# Conversion.net
KiCad netlist of a schematic drawn in Altium Designer
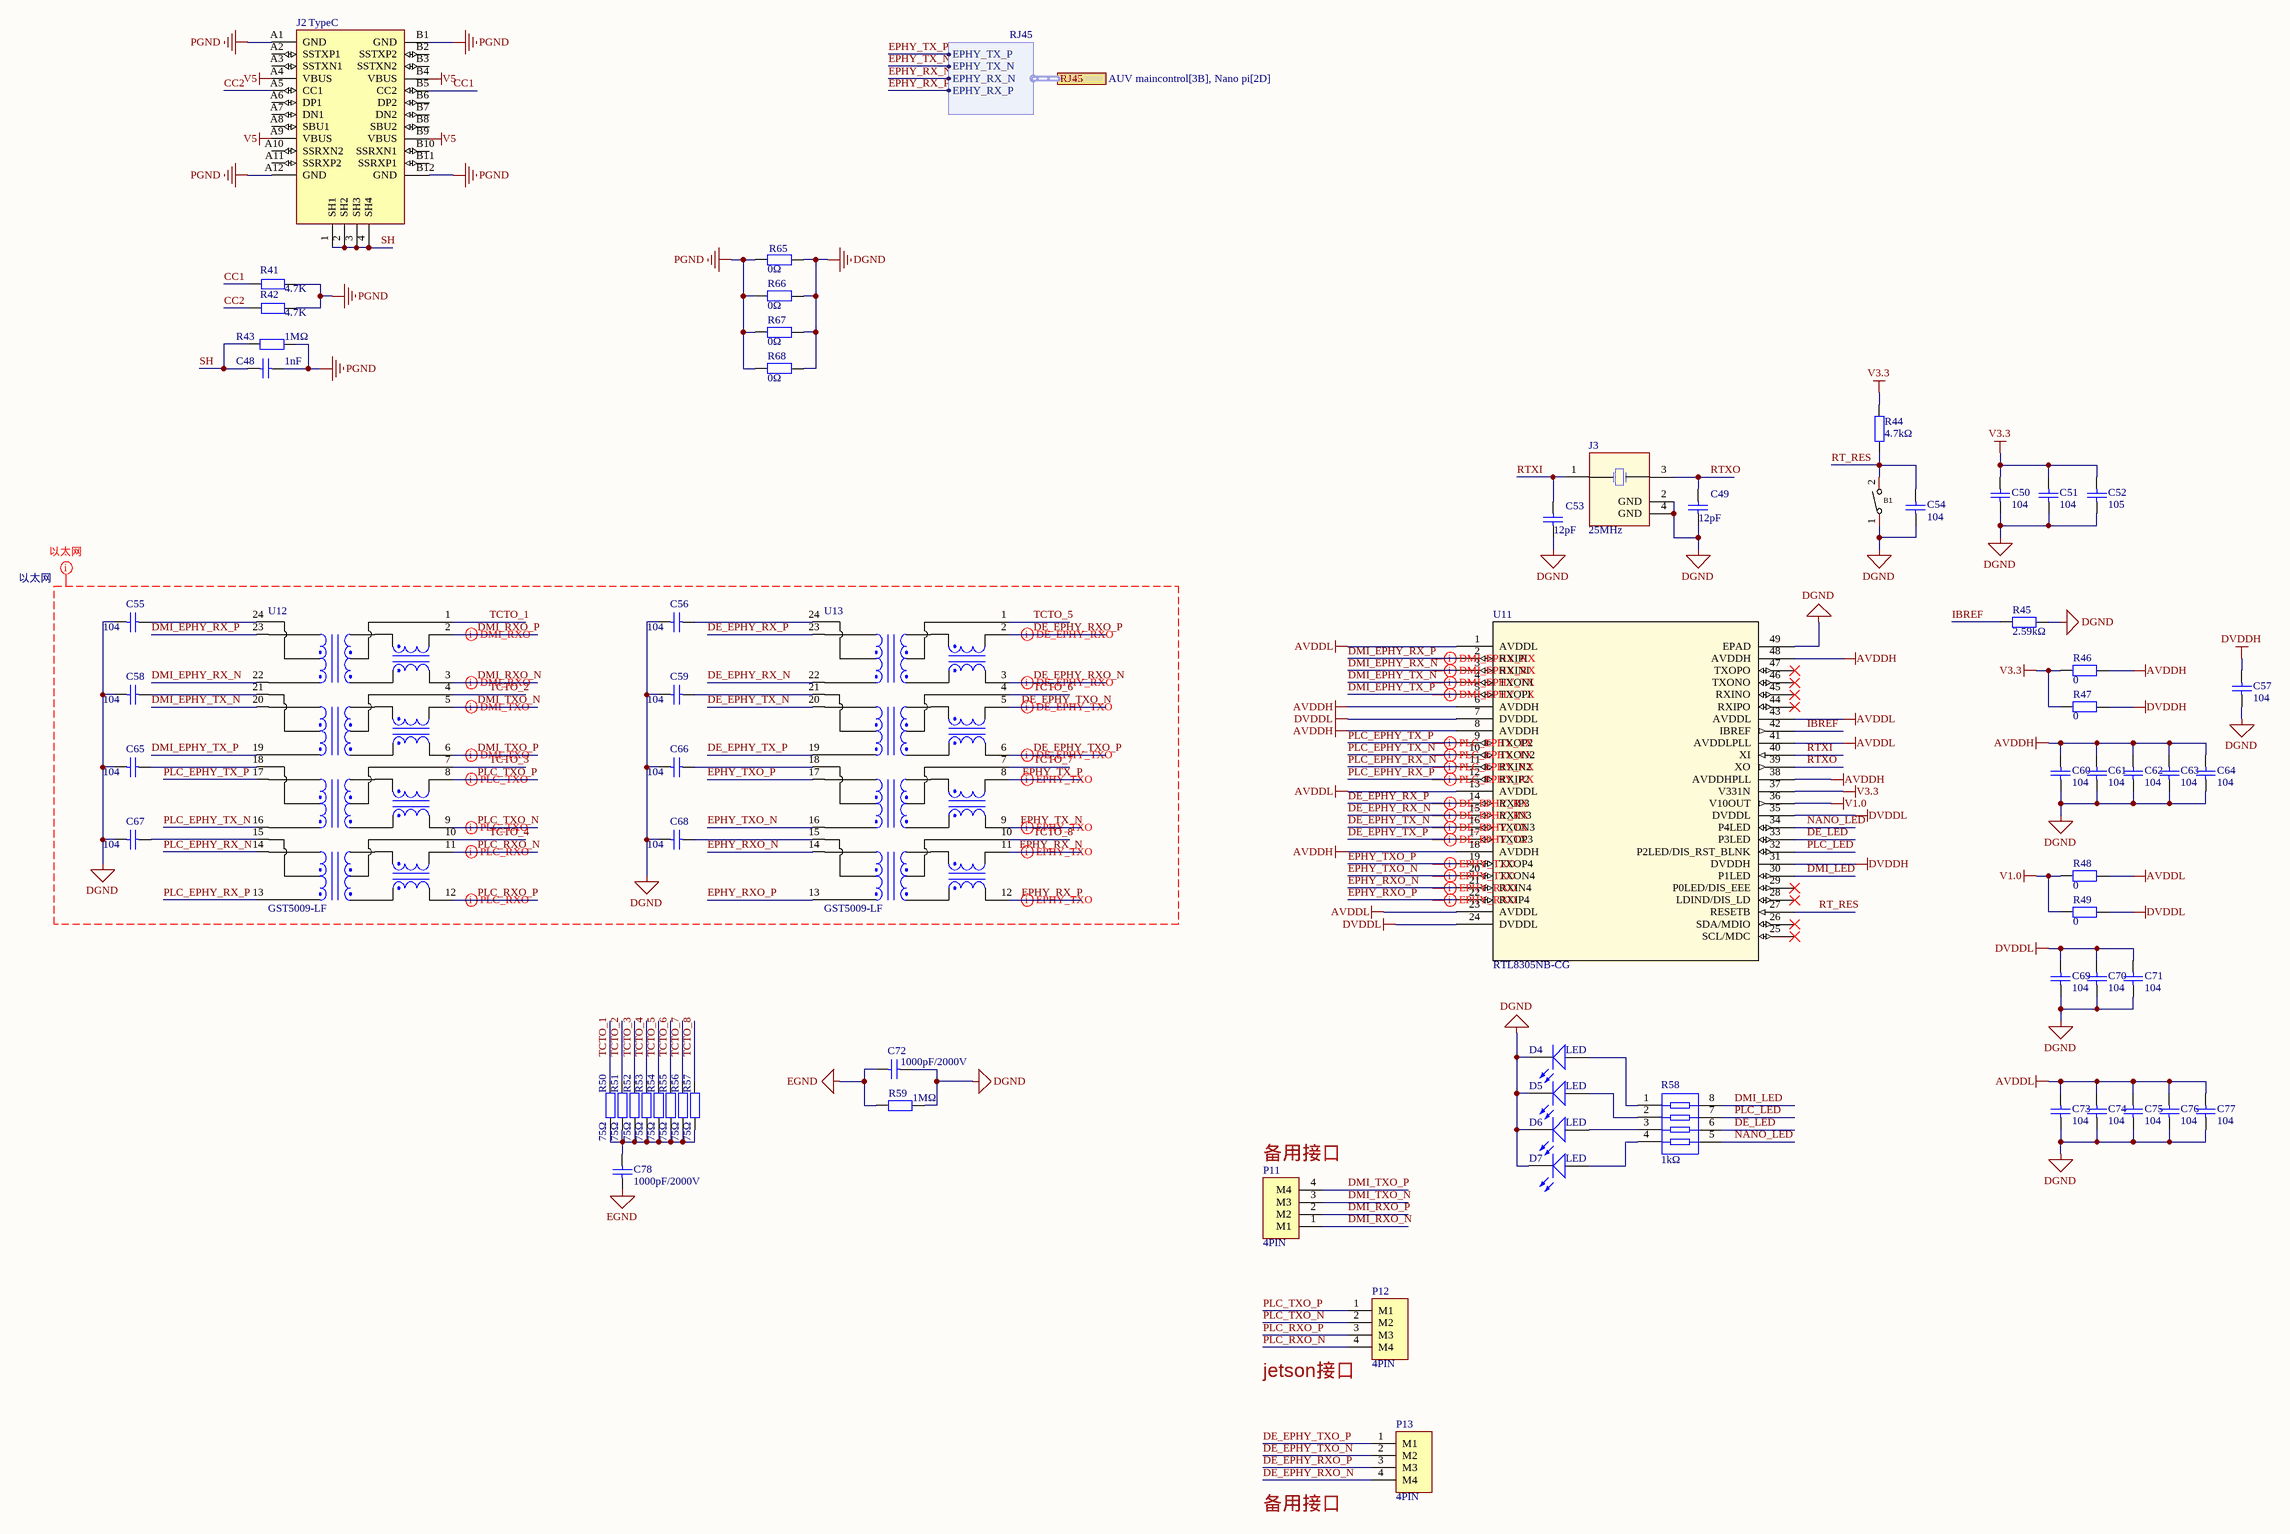
[diagram p0: Conversion.SchDoc]

(export (version "E")
  (design (tool "Eeschema 10.0.6"))
  (components
    (comp (ref "B1")
      (value "Bottom-2P-1Way")
      (footprint "SW-SMD_L4.0-W2.9-LS5.0")
      (description "轻触按键")
      (fields (field (name "MANUFACTURER") "SHOU HAN(首韩)") (field (name "MANUFACTURER PART") "TS342A2P-WZ"))
      (libsource (lib "PBK11") (part "Bottom-2P-1Way"))
    )
    (comp (ref "C48")
      (value "1nF")
      (footprint "1210_C")
      (description "贴片电容")
      (libsource (lib "SFerret") (part "SMT_Cap"))
    )
    (comp (ref "C49")
      (value "12pF")
      (footprint "0603_C")
      (description "贴片电容")
      (libsource (lib "SFerret") (part "SMT_Cap"))
    )
    (comp (ref "C50")
      (value "104")
      (footprint "0402_C")
      (description "贴片电容")
      (libsource (lib "SFerret") (part "SMT_Cap"))
    )
    (comp (ref "C51")
      (value "104")
      (footprint "0402_C")
      (description "贴片电容")
      (libsource (lib "SFerret") (part "SMT_Cap"))
    )
    (comp (ref "C52")
      (value "105")
      (footprint "0402_C")
      (description "贴片电容")
      (libsource (lib "SFerret") (part "SMT_Cap"))
    )
    (comp (ref "C53")
      (value "12pF")
      (footprint "0603_C")
      (description "贴片电容")
      (libsource (lib "SFerret") (part "SMT_Cap"))
    )
    (comp (ref "C54")
      (value "104")
      (footprint "0402_C")
      (description "贴片电容")
      (libsource (lib "SFerret") (part "SMT_Cap"))
    )
    (comp (ref "C55")
      (value "104")
      (footprint "0402_C")
      (description "贴片电容")
      (libsource (lib "SFerret") (part "SMT_Cap"))
    )
    (comp (ref "C56")
      (value "104")
      (footprint "0402_C")
      (description "贴片电容")
      (libsource (lib "SFerret") (part "SMT_Cap"))
    )
    (comp (ref "C57")
      (value "104")
      (footprint "0402_C")
      (description "贴片电容")
      (libsource (lib "SFerret") (part "SMT_Cap"))
    )
    (comp (ref "C58")
      (value "104")
      (footprint "0402_C")
      (description "贴片电容")
      (libsource (lib "SFerret") (part "SMT_Cap"))
    )
    (comp (ref "C59")
      (value "104")
      (footprint "0402_C")
      (description "贴片电容")
      (libsource (lib "SFerret") (part "SMT_Cap"))
    )
    (comp (ref "C60")
      (value "104")
      (footprint "0402_C")
      (description "贴片电容")
      (libsource (lib "SFerret") (part "SMT_Cap"))
    )
    (comp (ref "C61")
      (value "104")
      (footprint "0402_C")
      (description "贴片电容")
      (libsource (lib "SFerret") (part "SMT_Cap"))
    )
    (comp (ref "C62")
      (value "104")
      (footprint "0402_C")
      (description "贴片电容")
      (libsource (lib "SFerret") (part "SMT_Cap"))
    )
    (comp (ref "C63")
      (value "104")
      (footprint "0402_C")
      (description "贴片电容")
      (libsource (lib "SFerret") (part "SMT_Cap"))
    )
    (comp (ref "C64")
      (value "104")
      (footprint "0402_C")
      (description "贴片电容")
      (libsource (lib "SFerret") (part "SMT_Cap"))
    )
    (comp (ref "C65")
      (value "104")
      (footprint "0402_C")
      (description "贴片电容")
      (libsource (lib "SFerret") (part "SMT_Cap"))
    )
    (comp (ref "C66")
      (value "104")
      (footprint "0402_C")
      (description "贴片电容")
      (libsource (lib "SFerret") (part "SMT_Cap"))
    )
    (comp (ref "C67")
      (value "104")
      (footprint "0402_C")
      (description "贴片电容")
      (libsource (lib "SFerret") (part "SMT_Cap"))
    )
    (comp (ref "C68")
      (value "104")
      (footprint "0402_C")
      (description "贴片电容")
      (libsource (lib "SFerret") (part "SMT_Cap"))
    )
    (comp (ref "C69")
      (value "104")
      (footprint "0402_C")
      (description "贴片电容")
      (libsource (lib "SFerret") (part "SMT_Cap"))
    )
    (comp (ref "C70")
      (value "104")
      (footprint "0402_C")
      (description "贴片电容")
      (libsource (lib "SFerret") (part "SMT_Cap"))
    )
    (comp (ref "C71")
      (value "104")
      (footprint "0402_C")
      (description "贴片电容")
      (libsource (lib "SFerret") (part "SMT_Cap"))
    )
    (comp (ref "C72")
      (value "1000pF/2000V")
      (footprint "1210_C")
      (description "贴片电容")
      (libsource (lib "SFerret") (part "SMT_Cap"))
    )
    (comp (ref "C73")
      (value "104")
      (footprint "0402_C")
      (description "贴片电容")
      (libsource (lib "SFerret") (part "SMT_Cap"))
    )
    (comp (ref "C74")
      (value "104")
      (footprint "0402_C")
      (description "贴片电容")
      (libsource (lib "SFerret") (part "SMT_Cap"))
    )
    (comp (ref "C75")
      (value "104")
      (footprint "0402_C")
      (description "贴片电容")
      (libsource (lib "SFerret") (part "SMT_Cap"))
    )
    (comp (ref "C76")
      (value "104")
      (footprint "0402_C")
      (description "贴片电容")
      (libsource (lib "SFerret") (part "SMT_Cap"))
    )
    (comp (ref "C77")
      (value "104")
      (footprint "0402_C")
      (description "贴片电容")
      (libsource (lib "SFerret") (part "SMT_Cap"))
    )
    (comp (ref "C78")
      (value "1000pF/2000V")
      (footprint "1210_C")
      (description "贴片电容")
      (libsource (lib "SFerret") (part "SMT_Cap"))
    )
    (comp (ref "D4")
      (value "LED")
      (footprint "0805_LED")
      (description "发光二极管")
      (libsource (lib "SFerret") (part "LED"))
    )
    (comp (ref "D5")
      (value "LED")
      (footprint "0805_LED")
      (description "发光二极管")
      (libsource (lib "SFerret") (part "LED"))
    )
    (comp (ref "D6")
      (value "LED")
      (footprint "0805_LED")
      (description "发光二极管")
      (libsource (lib "SFerret") (part "LED"))
    )
    (comp (ref "D7")
      (value "LED")
      (footprint "0805_LED")
      (description "发光二极管")
      (libsource (lib "SFerret") (part "LED"))
    )
    (comp (ref "J2") (value "TypeC") (footprint "TYPE-C 16P") (libsource (lib "集大电协1.5") (part "TypeC")))
    (comp (ref "J3")
      (value "25MHz")
      (footprint "SMD-3225_4P")
      (libsource (lib "SFerret") (part "Oscillator_SMT_4P"))
    )
    (comp (ref "P11") (value "4PIN") (footprint "MX1.25S-4P") (libsource (lib "") (part "接线端子-4PIN_1")))
    (comp (ref "P12") (value "4PIN") (footprint "MX1.25S-4P") (libsource (lib "集大电协1.5") (part "接线端子-4PIN")))
    (comp (ref "P13") (value "4PIN") (footprint "MX1.25S-4P") (libsource (lib "集大电协1.5") (part "接线端子-4PIN")))
    (comp (ref "R41")
      (value "4.7K")
      (footprint "0603R")
      (description "电阻")
      (libsource (lib "集大电协1.5") (part "Res"))
    )
    (comp (ref "R42")
      (value "4.7K")
      (footprint "0603R")
      (description "电阻")
      (libsource (lib "集大电协1.5") (part "Res"))
    )
    (comp (ref "R43")
      (value "1MΩ")
      (footprint "1206_R")
      (description "贴片电阻")
      (libsource (lib "SFerret") (part "SMT_Res"))
    )
    (comp (ref "R44")
      (value "4.7kΩ")
      (footprint "0402_R")
      (description "贴片电阻")
      (libsource (lib "") (part "SMT_Res_2"))
    )
    (comp (ref "R45")
      (value "2.59kΩ")
      (footprint "0402_R")
      (description "贴片电阻")
      (libsource (lib "") (part "SMT_Res_1"))
    )
    (comp (ref "R46")
      (value "0")
      (footprint "0402_R")
      (description "贴片电阻")
      (libsource (lib "") (part "SMT_Res_1"))
    )
    (comp (ref "R47")
      (value "0")
      (footprint "0402_R")
      (description "贴片电阻")
      (libsource (lib "") (part "SMT_Res_1"))
    )
    (comp (ref "R48")
      (value "0")
      (footprint "0402_R")
      (description "贴片电阻")
      (libsource (lib "") (part "SMT_Res_1"))
    )
    (comp (ref "R49")
      (value "0")
      (footprint "0402_R")
      (description "贴片电阻")
      (libsource (lib "") (part "SMT_Res_1"))
    )
    (comp (ref "R50")
      (value "75Ω")
      (footprint "0402_R")
      (description "贴片电阻")
      (libsource (lib "") (part "SMT_Res_2"))
    )
    (comp (ref "R51")
      (value "75Ω")
      (footprint "0402_R")
      (description "贴片电阻")
      (libsource (lib "") (part "SMT_Res_2"))
    )
    (comp (ref "R52")
      (value "75Ω")
      (footprint "0402_R")
      (description "贴片电阻")
      (libsource (lib "") (part "SMT_Res_2"))
    )
    (comp (ref "R53")
      (value "75Ω")
      (footprint "0402_R")
      (description "贴片电阻")
      (libsource (lib "") (part "SMT_Res_2"))
    )
    (comp (ref "R54")
      (value "75Ω")
      (footprint "0402_R")
      (description "贴片电阻")
      (libsource (lib "") (part "SMT_Res_2"))
    )
    (comp (ref "R55")
      (value "75Ω")
      (footprint "0402_R")
      (description "贴片电阻")
      (libsource (lib "") (part "SMT_Res_2"))
    )
    (comp (ref "R56")
      (value "75Ω")
      (footprint "0402_R")
      (description "贴片电阻")
      (libsource (lib "") (part "SMT_Res_2"))
    )
    (comp (ref "R57")
      (value "75Ω")
      (footprint "0402_R")
      (description "贴片电阻")
      (libsource (lib "") (part "SMT_Res_2"))
    )
    (comp (ref "R58")
      (value "1kΩ")
      (footprint "0603_Rx4")
      (description "贴片排阻")
      (libsource (lib "SFerret") (part "SMT_Res-4"))
    )
    (comp (ref "R59")
      (value "1MΩ")
      (footprint "0603_R")
      (description "贴片电阻")
      (libsource (lib "SFerret") (part "SMT_Res"))
    )
    (comp (ref "R65")
      (value "0Ω")
      (footprint "1206_R")
      (description "贴片电阻")
      (libsource (lib "SFerret") (part "SMT_Res"))
    )
    (comp (ref "R66")
      (value "0Ω")
      (footprint "1206_R")
      (description "贴片电阻")
      (libsource (lib "SFerret") (part "SMT_Res"))
    )
    (comp (ref "R67")
      (value "0Ω")
      (footprint "1206_R")
      (description "贴片电阻")
      (libsource (lib "SFerret") (part "SMT_Res"))
    )
    (comp (ref "R68")
      (value "0Ω")
      (footprint "1206_R")
      (description "贴片电阻")
      (libsource (lib "SFerret") (part "SMT_Res"))
    )
    (comp (ref "U11")
      (value "RTL8305NB-CG")
      (footprint "QFN48_RTL8305_RTK-M")
      (description "10/100M PHY")
      (fields (field (name "COPYRIGHT") "Copyright (C) 2023 Ultra Librarian. All rights reserved."))
      (libsource (lib "SFerret") (part "RTL8305NB-CG"))
    )
    (comp (ref "U12")
      (value "GST5009-LF")
      (footprint "SOP100P1000X400-24N")
      (description "Network")
      (libsource (lib "SFerret") (part "GST5009-LF"))
    )
    (comp (ref "U13")
      (value "GST5009-LF")
      (footprint "SOP100P1000X400-24N")
      (description "Network")
      (libsource (lib "SFerret") (part "GST5009-LF"))
    )
  )
  (nets
    (net (code "2") (name "/CC1") (class "Default")
      (node (ref "J2") (pin "B5") (pinfunction "CC2_B5") (pintype "bidirectional"))
      (node (ref "R41") (pin "1") (pinfunction "1_1") (pintype "passive"))
    )
    (net (code "3") (name "/CC2") (class "Default")
      (node (ref "J2") (pin "A5") (pinfunction "CC1_A5") (pintype "bidirectional"))
      (node (ref "R42") (pin "1") (pinfunction "1_1") (pintype "passive"))
    )
    (net (code "4") (name "/DE_EPHY_RXO_N") (class "Default")
      (node (ref "P13") (pin "4") (pinfunction "M4_4") (pintype "passive"))
      (node (ref "U13") (pin "3") (pinfunction "16_3") (pintype "passive"))
    )
    (net (code "5") (name "/DE_EPHY_RXO_P") (class "Default")
      (node (ref "P13") (pin "3") (pinfunction "M3_3") (pintype "passive"))
      (node (ref "U13") (pin "2") (pinfunction "2_2") (pintype "passive"))
    )
    (net (code "6") (name "/DE_EPHY_RX_N") (class "Default")
      (node (ref "U11") (pin "15") (pinfunction "RXIN3_15") (pintype "bidirectional"))
      (node (ref "U13") (pin "22") (pinfunction "22_22") (pintype "passive"))
    )
    (net (code "7") (name "/DE_EPHY_RX_P") (class "Default")
      (node (ref "U11") (pin "14") (pinfunction "RXIP3_14") (pintype "bidirectional"))
      (node (ref "U13") (pin "23") (pinfunction "23_23") (pintype "passive"))
    )
    (net (code "8") (name "/DE_EPHY_TXO_N") (class "Default")
      (node (ref "P13") (pin "2") (pinfunction "M2_2") (pintype "passive"))
      (node (ref "U13") (pin "5") (pinfunction "5_5") (pintype "passive"))
    )
    (net (code "9") (name "/DE_EPHY_TXO_P") (class "Default")
      (node (ref "P13") (pin "1") (pinfunction "M1_1") (pintype "passive"))
      (node (ref "U13") (pin "6") (pinfunction "6_6") (pintype "passive"))
    )
    (net (code "10") (name "/DE_EPHY_TX_N") (class "Default")
      (node (ref "U11") (pin "16") (pinfunction "TXON3_16") (pintype "bidirectional"))
      (node (ref "U13") (pin "20") (pinfunction "20_20") (pintype "passive"))
    )
    (net (code "11") (name "/DE_EPHY_TX_P") (class "Default")
      (node (ref "U11") (pin "17") (pinfunction "TXOP3_17") (pintype "bidirectional"))
      (node (ref "U13") (pin "19") (pinfunction "19_19") (pintype "passive"))
    )
    (net (code "12") (name "/DE_LED") (class "Default")
      (node (ref "R58") (pin "6") (pinfunction "6_6") (pintype "passive"))
      (node (ref "U11") (pin "33") (pinfunction "P3LED_33") (pintype "bidirectional"))
    )
    (net (code "13") (name "/DMI_EPHY_RX_N") (class "Default")
      (node (ref "U11") (pin "3") (pinfunction "RXINI_3") (pintype "bidirectional"))
      (node (ref "U12") (pin "22") (pinfunction "22_22") (pintype "passive"))
    )
    (net (code "14") (name "/DMI_EPHY_RX_P") (class "Default")
      (node (ref "U11") (pin "2") (pinfunction "RXIPI_2") (pintype "bidirectional"))
      (node (ref "U12") (pin "23") (pinfunction "23_23") (pintype "passive"))
    )
    (net (code "15") (name "/DMI_EPHY_TX_N") (class "Default")
      (node (ref "U11") (pin "4") (pinfunction "TXONI_4") (pintype "bidirectional"))
      (node (ref "U12") (pin "20") (pinfunction "20_20") (pintype "passive"))
    )
    (net (code "16") (name "/DMI_EPHY_TX_P") (class "Default")
      (node (ref "U11") (pin "5") (pinfunction "TXOPI_5") (pintype "bidirectional"))
      (node (ref "U12") (pin "19") (pinfunction "19_19") (pintype "passive"))
    )
    (net (code "17") (name "/DMI_LED") (class "Default")
      (node (ref "R58") (pin "8") (pinfunction "8_8") (pintype "passive"))
      (node (ref "U11") (pin "30") (pinfunction "P1LED_30") (pintype "bidirectional"))
    )
    (net (code "18") (name "/DMI_RXO_N") (class "Default")
      (node (ref "P11") (pin "1") (pinfunction "M1_1") (pintype "passive"))
      (node (ref "U12") (pin "3") (pinfunction "16_3") (pintype "passive"))
    )
    (net (code "19") (name "/DMI_RXO_P") (class "Default")
      (node (ref "P11") (pin "2") (pinfunction "M2_2") (pintype "passive"))
      (node (ref "U12") (pin "2") (pinfunction "2_2") (pintype "passive"))
    )
    (net (code "20") (name "/DMI_TXO_N") (class "Default")
      (node (ref "P11") (pin "3") (pinfunction "M3_3") (pintype "passive"))
      (node (ref "U12") (pin "5") (pinfunction "5_5") (pintype "passive"))
    )
    (net (code "21") (name "/DMI_TXO_P") (class "Default")
      (node (ref "P11") (pin "4") (pinfunction "M4_4") (pintype "passive"))
      (node (ref "U12") (pin "6") (pinfunction "6_6") (pintype "passive"))
    )
    (net (code "22") (name "/EPHY_RXO_N") (class "Default")
      (node (ref "U11") (pin "21") (pinfunction "RXIN4_21") (pintype "bidirectional"))
      (node (ref "U13") (pin "14") (pinfunction "14_14") (pintype "passive"))
    )
    (net (code "23") (name "/EPHY_RXO_P") (class "Default")
      (node (ref "U11") (pin "22") (pinfunction "RXIP4_22") (pintype "bidirectional"))
      (node (ref "U13") (pin "13") (pinfunction "13_13") (pintype "passive"))
    )
    (net (code "24") (name "/EPHY_RX_N") (class "Default")
      (node (ref "U13") (pin "11") (pinfunction "11_11") (pintype "passive"))
    )
    (net (code "25") (name "/EPHY_RX_P") (class "Default")
      (node (ref "U13") (pin "12") (pinfunction "12_12") (pintype "passive"))
    )
    (net (code "26") (name "/EPHY_TXO_N") (class "Default")
      (node (ref "U11") (pin "20") (pinfunction "TXON4_20") (pintype "bidirectional"))
      (node (ref "U13") (pin "16") (pinfunction "16_16") (pintype "passive"))
    )
    (net (code "27") (name "/EPHY_TXO_P") (class "Default")
      (node (ref "U11") (pin "19") (pinfunction "TXOP4_19") (pintype "bidirectional"))
      (node (ref "U13") (pin "17") (pinfunction "17_17") (pintype "passive"))
    )
    (net (code "28") (name "/EPHY_TX_N") (class "Default")
      (node (ref "U13") (pin "9") (pinfunction "9_9") (pintype "passive"))
    )
    (net (code "29") (name "/EPHY_TX_P") (class "Default")
      (node (ref "U13") (pin "8") (pinfunction "8_8") (pintype "passive"))
    )
    (net (code "30") (name "/IBREF") (class "Default")
      (node (ref "R45") (pin "2") (pinfunction "2_2") (pintype "passive"))
      (node (ref "U11") (pin "42") (pinfunction "IBREF_42") (pintype "output"))
    )
    (net (code "31") (name "/NANO_LED") (class "Default")
      (node (ref "R58") (pin "5") (pinfunction "5_5") (pintype "passive"))
      (node (ref "U11") (pin "34") (pinfunction "P4LED_34") (pintype "bidirectional"))
    )
    (net (code "32") (name "/PLC_EPHY_RX_N") (class "Default")
      (node (ref "U11") (pin "11") (pinfunction "RXIN2_11") (pintype "bidirectional"))
      (node (ref "U12") (pin "14") (pinfunction "14_14") (pintype "passive"))
    )
    (net (code "33") (name "/PLC_EPHY_RX_P") (class "Default")
      (node (ref "U11") (pin "12") (pinfunction "RXIP2_12") (pintype "bidirectional"))
      (node (ref "U12") (pin "13") (pinfunction "13_13") (pintype "passive"))
    )
    (net (code "34") (name "/PLC_EPHY_TX_N") (class "Default")
      (node (ref "U11") (pin "10") (pinfunction "TXON2_10") (pintype "bidirectional"))
      (node (ref "U12") (pin "16") (pinfunction "16_16") (pintype "passive"))
    )
    (net (code "35") (name "/PLC_EPHY_TX_P") (class "Default")
      (node (ref "U11") (pin "9") (pinfunction "TXOP2_9") (pintype "bidirectional"))
      (node (ref "U12") (pin "17") (pinfunction "17_17") (pintype "passive"))
    )
    (net (code "36") (name "/PLC_LED") (class "Default")
      (node (ref "R58") (pin "7") (pinfunction "7_7") (pintype "passive"))
      (node (ref "U11") (pin "32") (pinfunction "P2LED/DIS_RST_BLNK_32") (pintype "bidirectional"))
    )
    (net (code "37") (name "/PLC_RXO_N") (class "Default")
      (node (ref "P12") (pin "4") (pinfunction "M4_4") (pintype "passive"))
      (node (ref "U12") (pin "11") (pinfunction "11_11") (pintype "passive"))
    )
    (net (code "38") (name "/PLC_RXO_P") (class "Default")
      (node (ref "P12") (pin "3") (pinfunction "M3_3") (pintype "passive"))
      (node (ref "U12") (pin "12") (pinfunction "12_12") (pintype "passive"))
    )
    (net (code "39") (name "/PLC_TXO_N") (class "Default")
      (node (ref "P12") (pin "2") (pinfunction "M2_2") (pintype "passive"))
      (node (ref "U12") (pin "9") (pinfunction "9_9") (pintype "passive"))
    )
    (net (code "40") (name "/PLC_TXO_P") (class "Default")
      (node (ref "P12") (pin "1") (pinfunction "M1_1") (pintype "passive"))
      (node (ref "U12") (pin "8") (pinfunction "8_8") (pintype "passive"))
    )
    (net (code "41") (name "/RTXI") (class "Default")
      (node (ref "C53") (pin "2") (pinfunction "2_2") (pintype "passive"))
      (node (ref "J3") (pin "1") (pinfunction "OSC1_1") (pintype "passive"))
      (node (ref "U11") (pin "40") (pinfunction "XI_40") (pintype "input"))
    )
    (net (code "42") (name "/RTXO") (class "Default")
      (node (ref "C49") (pin "2") (pinfunction "2_2") (pintype "passive"))
      (node (ref "J3") (pin "3") (pinfunction "OSC2_3") (pintype "passive"))
      (node (ref "U11") (pin "39") (pinfunction "XO_39") (pintype "output"))
    )
    (net (code "43") (name "/RT_RES") (class "Default")
      (node (ref "B1") (pin "2") (pinfunction "2_2") (pintype "passive"))
      (node (ref "C54") (pin "2") (pinfunction "2_2") (pintype "passive"))
      (node (ref "R44") (pin "1") (pinfunction "1_1") (pintype "passive"))
      (node (ref "U11") (pin "27") (pinfunction "RESETB_27") (pintype "input"))
    )
    (net (code "44") (name "/SH") (class "Default")
      (node (ref "C48") (pin "1") (pinfunction "1_1") (pintype "passive"))
      (node (ref "J2") (pin "1") (pinfunction "SH1_1") (pintype "power_in"))
      (node (ref "J2") (pin "2") (pinfunction "SH2_2") (pintype "power_in"))
      (node (ref "J2") (pin "3") (pinfunction "SH3_3") (pintype "power_in"))
      (node (ref "J2") (pin "4") (pinfunction "SH4_4") (pintype "power_in"))
      (node (ref "R43") (pin "1") (pinfunction "1_1") (pintype "passive"))
    )
    (net (code "45") (name "/TCTO_1") (class "Default")
      (node (ref "R50") (pin "2") (pinfunction "2_2") (pintype "passive"))
      (node (ref "U12") (pin "1") (pinfunction "1_1") (pintype "passive"))
    )
    (net (code "46") (name "/TCTO_2") (class "Default")
      (node (ref "R51") (pin "2") (pinfunction "2_2") (pintype "passive"))
      (node (ref "U12") (pin "4") (pinfunction "4_4") (pintype "passive"))
    )
    (net (code "47") (name "/TCTO_3") (class "Default")
      (node (ref "R52") (pin "2") (pinfunction "2_2") (pintype "passive"))
      (node (ref "U12") (pin "7") (pinfunction "7_7") (pintype "passive"))
    )
    (net (code "48") (name "/TCTO_4") (class "Default")
      (node (ref "R53") (pin "2") (pinfunction "2_2") (pintype "passive"))
      (node (ref "U12") (pin "10") (pinfunction "10_10") (pintype "passive"))
    )
    (net (code "49") (name "/TCTO_5") (class "Default")
      (node (ref "R54") (pin "2") (pinfunction "2_2") (pintype "passive"))
      (node (ref "U13") (pin "1") (pinfunction "1_1") (pintype "passive"))
    )
    (net (code "50") (name "/TCTO_6") (class "Default")
      (node (ref "R55") (pin "2") (pinfunction "2_2") (pintype "passive"))
      (node (ref "U13") (pin "4") (pinfunction "4_4") (pintype "passive"))
    )
    (net (code "51") (name "/TCTO_7") (class "Default")
      (node (ref "R56") (pin "2") (pinfunction "2_2") (pintype "passive"))
      (node (ref "U13") (pin "7") (pinfunction "7_7") (pintype "passive"))
    )
    (net (code "52") (name "/TCTO_8") (class "Default")
      (node (ref "R57") (pin "2") (pinfunction "2_2") (pintype "passive"))
      (node (ref "U13") (pin "10") (pinfunction "10_10") (pintype "passive"))
    )
    (net (code "54") (name "AVDDH") (class "Default")
      (node (ref "C60") (pin "1") (pinfunction "1_1") (pintype "passive"))
      (node (ref "C61") (pin "1") (pinfunction "1_1") (pintype "passive"))
      (node (ref "C62") (pin "1") (pinfunction "1_1") (pintype "passive"))
      (node (ref "C63") (pin "1") (pinfunction "1_1") (pintype "passive"))
      (node (ref "C64") (pin "1") (pinfunction "1_1") (pintype "passive"))
      (node (ref "R46") (pin "1") (pinfunction "1_1") (pintype "passive"))
      (node (ref "U11") (pin "18") (pinfunction "AVDDH_18") (pintype "power_in"))
      (node (ref "U11") (pin "38") (pinfunction "AVDDHPLL_38") (pintype "power_in"))
      (node (ref "U11") (pin "48") (pinfunction "AVDDH_48") (pintype "power_in"))
      (node (ref "U11") (pin "6") (pinfunction "AVDDH_6") (pintype "power_in"))
      (node (ref "U11") (pin "8") (pinfunction "AVDDH_8") (pintype "power_in"))
    )
    (net (code "55") (name "AVDDL") (class "Default")
      (node (ref "C73") (pin "1") (pinfunction "1_1") (pintype "passive"))
      (node (ref "C74") (pin "1") (pinfunction "1_1") (pintype "passive"))
      (node (ref "C75") (pin "1") (pinfunction "1_1") (pintype "passive"))
      (node (ref "C76") (pin "1") (pinfunction "1_1") (pintype "passive"))
      (node (ref "C77") (pin "1") (pinfunction "1_1") (pintype "passive"))
      (node (ref "R48") (pin "1") (pinfunction "1_1") (pintype "passive"))
      (node (ref "U11") (pin "1") (pinfunction "AVDDL_1") (pintype "power_in"))
      (node (ref "U11") (pin "13") (pinfunction "AVDDL_13") (pintype "power_in"))
      (node (ref "U11") (pin "23") (pinfunction "AVDDL_23") (pintype "power_in"))
      (node (ref "U11") (pin "41") (pinfunction "AVDDLPLL_41") (pintype "power_in"))
      (node (ref "U11") (pin "43") (pinfunction "AVDDL_43") (pintype "power_in"))
    )
    (net (code "56") (name "DGND") (class "Default")
      (node (ref "B1") (pin "1") (pinfunction "1_1") (pintype "passive"))
      (node (ref "C49") (pin "1") (pinfunction "1_1") (pintype "passive"))
      (node (ref "C50") (pin "1") (pinfunction "1_1") (pintype "passive"))
      (node (ref "C51") (pin "1") (pinfunction "1_1") (pintype "passive"))
      (node (ref "C52") (pin "1") (pinfunction "1_1") (pintype "passive"))
      (node (ref "C53") (pin "1") (pinfunction "1_1") (pintype "passive"))
      (node (ref "C54") (pin "1") (pinfunction "1_1") (pintype "passive"))
      (node (ref "C55") (pin "2") (pinfunction "2_2") (pintype "passive"))
      (node (ref "C56") (pin "2") (pinfunction "2_2") (pintype "passive"))
      (node (ref "C57") (pin "2") (pinfunction "2_2") (pintype "passive"))
      (node (ref "C58") (pin "2") (pinfunction "2_2") (pintype "passive"))
      (node (ref "C59") (pin "2") (pinfunction "2_2") (pintype "passive"))
      (node (ref "C60") (pin "2") (pinfunction "2_2") (pintype "passive"))
      (node (ref "C61") (pin "2") (pinfunction "2_2") (pintype "passive"))
      (node (ref "C62") (pin "2") (pinfunction "2_2") (pintype "passive"))
      (node (ref "C63") (pin "2") (pinfunction "2_2") (pintype "passive"))
      (node (ref "C64") (pin "2") (pinfunction "2_2") (pintype "passive"))
      (node (ref "C65") (pin "2") (pinfunction "2_2") (pintype "passive"))
      (node (ref "C66") (pin "2") (pinfunction "2_2") (pintype "passive"))
      (node (ref "C67") (pin "2") (pinfunction "2_2") (pintype "passive"))
      (node (ref "C68") (pin "2") (pinfunction "2_2") (pintype "passive"))
      (node (ref "C69") (pin "2") (pinfunction "2_2") (pintype "passive"))
      (node (ref "C70") (pin "2") (pinfunction "2_2") (pintype "passive"))
      (node (ref "C71") (pin "2") (pinfunction "2_2") (pintype "passive"))
      (node (ref "C72") (pin "1") (pinfunction "1_1") (pintype "passive"))
      (node (ref "C73") (pin "2") (pinfunction "2_2") (pintype "passive"))
      (node (ref "C74") (pin "2") (pinfunction "2_2") (pintype "passive"))
      (node (ref "C75") (pin "2") (pinfunction "2_2") (pintype "passive"))
      (node (ref "C76") (pin "2") (pinfunction "2_2") (pintype "passive"))
      (node (ref "C77") (pin "2") (pinfunction "2_2") (pintype "passive"))
      (node (ref "D4") (pin "K") (pinfunction "K_K") (pintype "passive"))
      (node (ref "D5") (pin "K") (pinfunction "K_K") (pintype "passive"))
      (node (ref "D6") (pin "K") (pinfunction "K_K") (pintype "passive"))
      (node (ref "D7") (pin "K") (pinfunction "K_K") (pintype "passive"))
      (node (ref "J3") (pin "2") (pinfunction "GND_2") (pintype "passive"))
      (node (ref "J3") (pin "4") (pinfunction "GND_4") (pintype "passive"))
      (node (ref "R45") (pin "1") (pinfunction "1_1") (pintype "passive"))
      (node (ref "R59") (pin "2") (pinfunction "2_2") (pintype "passive"))
      (node (ref "R65") (pin "2") (pinfunction "2_2") (pintype "passive"))
      (node (ref "R66") (pin "2") (pinfunction "2_2") (pintype "passive"))
      (node (ref "R67") (pin "2") (pinfunction "2_2") (pintype "passive"))
      (node (ref "R68") (pin "2") (pinfunction "2_2") (pintype "passive"))
      (node (ref "U11") (pin "49") (pinfunction "EPAD_49") (pintype "power_in"))
    )
    (net (code "57") (name "DVDDH") (class "Default")
      (node (ref "C57") (pin "1") (pinfunction "1_1") (pintype "passive"))
      (node (ref "R47") (pin "1") (pinfunction "1_1") (pintype "passive"))
      (node (ref "U11") (pin "31") (pinfunction "DVDDH_31") (pintype "power_in"))
    )
    (net (code "58") (name "DVDDL") (class "Default")
      (node (ref "C69") (pin "1") (pinfunction "1_1") (pintype "passive"))
      (node (ref "C70") (pin "1") (pinfunction "1_1") (pintype "passive"))
      (node (ref "C71") (pin "1") (pinfunction "1_1") (pintype "passive"))
      (node (ref "R49") (pin "1") (pinfunction "1_1") (pintype "passive"))
      (node (ref "U11") (pin "24") (pinfunction "DVDDL_24") (pintype "power_in"))
      (node (ref "U11") (pin "35") (pinfunction "DVDDL_35") (pintype "power_in"))
      (node (ref "U11") (pin "7") (pinfunction "DVDDL_7") (pintype "power_in"))
    )
    (net (code "59") (name "EGND") (class "Default")
      (node (ref "C72") (pin "2") (pinfunction "2_2") (pintype "passive"))
      (node (ref "C78") (pin "1") (pinfunction "1_1") (pintype "passive"))
      (node (ref "R59") (pin "1") (pinfunction "1_1") (pintype "passive"))
    )
    (net (code "60") (name "Net-(C55-Pad1)") (class "Default")
      (node (ref "C55") (pin "1") (pinfunction "1_1") (pintype "passive"))
      (node (ref "U12") (pin "24") (pinfunction "24_24") (pintype "passive"))
    )
    (net (code "61") (name "Net-(C56-Pad1)") (class "Default")
      (node (ref "C56") (pin "1") (pinfunction "1_1") (pintype "passive"))
      (node (ref "U13") (pin "24") (pinfunction "24_24") (pintype "passive"))
    )
    (net (code "62") (name "Net-(C58-Pad1)") (class "Default")
      (node (ref "C58") (pin "1") (pinfunction "1_1") (pintype "passive"))
      (node (ref "U12") (pin "21") (pinfunction "21_21") (pintype "passive"))
    )
    (net (code "63") (name "Net-(C59-Pad1)") (class "Default")
      (node (ref "C59") (pin "1") (pinfunction "1_1") (pintype "passive"))
      (node (ref "U13") (pin "21") (pinfunction "21_21") (pintype "passive"))
    )
    (net (code "64") (name "Net-(C65-Pad1)") (class "Default")
      (node (ref "C65") (pin "1") (pinfunction "1_1") (pintype "passive"))
      (node (ref "U12") (pin "18") (pinfunction "18_18") (pintype "passive"))
    )
    (net (code "65") (name "Net-(C66-Pad1)") (class "Default")
      (node (ref "C66") (pin "1") (pinfunction "1_1") (pintype "passive"))
      (node (ref "U13") (pin "18") (pinfunction "18_18") (pintype "passive"))
    )
    (net (code "66") (name "Net-(C67-Pad1)") (class "Default")
      (node (ref "C67") (pin "1") (pinfunction "1_1") (pintype "passive"))
      (node (ref "U12") (pin "15") (pinfunction "15_15") (pintype "passive"))
    )
    (net (code "67") (name "Net-(C68-Pad1)") (class "Default")
      (node (ref "C68") (pin "1") (pinfunction "1_1") (pintype "passive"))
      (node (ref "U13") (pin "15") (pinfunction "15_15") (pintype "passive"))
    )
    (net (code "68") (name "Net-(C78-Pad2)") (class "Default")
      (node (ref "C78") (pin "2") (pinfunction "2_2") (pintype "passive"))
      (node (ref "R50") (pin "1") (pinfunction "1_1") (pintype "passive"))
      (node (ref "R51") (pin "1") (pinfunction "1_1") (pintype "passive"))
      (node (ref "R52") (pin "1") (pinfunction "1_1") (pintype "passive"))
      (node (ref "R53") (pin "1") (pinfunction "1_1") (pintype "passive"))
      (node (ref "R54") (pin "1") (pinfunction "1_1") (pintype "passive"))
      (node (ref "R55") (pin "1") (pinfunction "1_1") (pintype "passive"))
      (node (ref "R56") (pin "1") (pinfunction "1_1") (pintype "passive"))
      (node (ref "R57") (pin "1") (pinfunction "1_1") (pintype "passive"))
    )
    (net (code "69") (name "Net-(D4-PadA)") (class "Default")
      (node (ref "D4") (pin "A") (pinfunction "A_A") (pintype "passive"))
      (node (ref "R58") (pin "1") (pinfunction "1_1") (pintype "passive"))
    )
    (net (code "70") (name "Net-(D5-PadA)") (class "Default")
      (node (ref "D5") (pin "A") (pinfunction "A_A") (pintype "passive"))
      (node (ref "R58") (pin "2") (pinfunction "2_2") (pintype "passive"))
    )
    (net (code "71") (name "Net-(D6-PadA)") (class "Default")
      (node (ref "D6") (pin "A") (pinfunction "A_A") (pintype "passive"))
      (node (ref "R58") (pin "3") (pinfunction "3_3") (pintype "passive"))
    )
    (net (code "72") (name "Net-(D7-PadA)") (class "Default")
      (node (ref "D7") (pin "A") (pinfunction "A_A") (pintype "passive"))
      (node (ref "R58") (pin "4") (pinfunction "4_4") (pintype "passive"))
    )
    (net (code "73") (name "PGND") (class "Default")
      (node (ref "C48") (pin "2") (pinfunction "2_2") (pintype "passive"))
      (node (ref "J2") (pin "A1") (pinfunction "GND_A1") (pintype "power_in"))
      (node (ref "J2") (pin "A12") (pinfunction "GND_A12") (pintype "power_in"))
      (node (ref "J2") (pin "B1") (pinfunction "GND_B1") (pintype "power_in"))
      (node (ref "J2") (pin "B12") (pinfunction "GND_B12") (pintype "power_in"))
      (node (ref "R41") (pin "2") (pinfunction "2_2") (pintype "passive"))
      (node (ref "R42") (pin "2") (pinfunction "2_2") (pintype "passive"))
      (node (ref "R43") (pin "2") (pinfunction "2_2") (pintype "passive"))
      (node (ref "R65") (pin "1") (pinfunction "1_1") (pintype "passive"))
      (node (ref "R66") (pin "1") (pinfunction "1_1") (pintype "passive"))
      (node (ref "R67") (pin "1") (pinfunction "1_1") (pintype "passive"))
      (node (ref "R68") (pin "1") (pinfunction "1_1") (pintype "passive"))
    )
    (net (code "74") (name "V1.0") (class "Default")
      (node (ref "R48") (pin "2") (pinfunction "2_2") (pintype "passive"))
      (node (ref "R49") (pin "2") (pinfunction "2_2") (pintype "passive"))
      (node (ref "U11") (pin "36") (pinfunction "V10OUT_36") (pintype "output"))
    )
    (net (code "75") (name "V3.3") (class "Default")
      (node (ref "C50") (pin "2") (pinfunction "2_2") (pintype "passive"))
      (node (ref "C51") (pin "2") (pinfunction "2_2") (pintype "passive"))
      (node (ref "C52") (pin "2") (pinfunction "2_2") (pintype "passive"))
      (node (ref "R44") (pin "2") (pinfunction "2_2") (pintype "passive"))
      (node (ref "R46") (pin "2") (pinfunction "2_2") (pintype "passive"))
      (node (ref "R47") (pin "2") (pinfunction "2_2") (pintype "passive"))
      (node (ref "U11") (pin "37") (pinfunction "V331N_37") (pintype "power_in"))
    )
    (net (code "76") (name "V5") (class "Default")
      (node (ref "J2") (pin "A4") (pinfunction "VBUS_A4") (pintype "power_in"))
      (node (ref "J2") (pin "A9") (pinfunction "VBUS_A9") (pintype "power_in"))
      (node (ref "J2") (pin "B4") (pinfunction "VBUS_B4") (pintype "power_in"))
      (node (ref "J2") (pin "B9") (pinfunction "VBUS_B9") (pintype "power_in"))
    )
    (net (code "77") (name "unconnected-(J2-DN1-PadA7)") (class "Default")
      (node (ref "J2") (pin "A7") (pinfunction "DN1_A7") (pintype "bidirectional"))
    )
    (net (code "78") (name "unconnected-(J2-DN2-PadB7)") (class "Default")
      (node (ref "J2") (pin "B7") (pinfunction "DN2_B7") (pintype "bidirectional"))
    )
    (net (code "79") (name "unconnected-(J2-DP1-PadA6)") (class "Default")
      (node (ref "J2") (pin "A6") (pinfunction "DP1_A6") (pintype "bidirectional"))
    )
    (net (code "80") (name "unconnected-(J2-DP2-PadB6)") (class "Default")
      (node (ref "J2") (pin "B6") (pinfunction "DP2_B6") (pintype "bidirectional"))
    )
    (net (code "81") (name "unconnected-(J2-SBU1-PadA8)") (class "Default")
      (node (ref "J2") (pin "A8") (pinfunction "SBU1_A8") (pintype "bidirectional"))
    )
    (net (code "82") (name "unconnected-(J2-SBU2-PadB8)") (class "Default")
      (node (ref "J2") (pin "B8") (pinfunction "SBU2_B8") (pintype "bidirectional"))
    )
    (net (code "83") (name "unconnected-(J2-SSRXN1-PadB10)") (class "Default")
      (node (ref "J2") (pin "B10") (pinfunction "SSRXN1_B10") (pintype "bidirectional"))
    )
    (net (code "84") (name "unconnected-(J2-SSRXN2-PadA10)") (class "Default")
      (node (ref "J2") (pin "A10") (pinfunction "SSRXN2_A10") (pintype "bidirectional"))
    )
    (net (code "85") (name "unconnected-(J2-SSRXP1-PadB11)") (class "Default")
      (node (ref "J2") (pin "B11") (pinfunction "SSRXP1_B11") (pintype "bidirectional"))
    )
    (net (code "86") (name "unconnected-(J2-SSRXP2-PadA11)") (class "Default")
      (node (ref "J2") (pin "A11") (pinfunction "SSRXP2_A11") (pintype "bidirectional"))
    )
    (net (code "87") (name "unconnected-(J2-SSTXN1-PadA3)") (class "Default")
      (node (ref "J2") (pin "A3") (pinfunction "SSTXN1_A3") (pintype "bidirectional"))
    )
    (net (code "88") (name "unconnected-(J2-SSTXN2-PadB3)") (class "Default")
      (node (ref "J2") (pin "B3") (pinfunction "SSTXN2_B3") (pintype "bidirectional"))
    )
    (net (code "89") (name "unconnected-(J2-SSTXP1-PadA2)") (class "Default")
      (node (ref "J2") (pin "A2") (pinfunction "SSTXP1_A2") (pintype "bidirectional"))
    )
    (net (code "90") (name "unconnected-(J2-SSTXP2-PadB2)") (class "Default")
      (node (ref "J2") (pin "B2") (pinfunction "SSTXP2_B2") (pintype "bidirectional"))
    )
    (net (code "91") (name "unconnected-(U11-LDIND{slash}DIS_LD-Pad28)") (class "Default")
      (node (ref "U11") (pin "28") (pinfunction "LDIND/DIS_LD_28") (pintype "bidirectional+no_connect"))
    )
    (net (code "92") (name "unconnected-(U11-P0LED{slash}DIS_EEE-Pad29)") (class "Default")
      (node (ref "U11") (pin "29") (pinfunction "P0LED/DIS_EEE_29") (pintype "bidirectional+no_connect"))
    )
    (net (code "93") (name "unconnected-(U11-RXINO-Pad45)") (class "Default")
      (node (ref "U11") (pin "45") (pinfunction "RXINO_45") (pintype "bidirectional+no_connect"))
    )
    (net (code "94") (name "unconnected-(U11-RXIPO-Pad44)") (class "Default")
      (node (ref "U11") (pin "44") (pinfunction "RXIPO_44") (pintype "bidirectional+no_connect"))
    )
    (net (code "95") (name "unconnected-(U11-SCL{slash}MDC-Pad25)") (class "Default")
      (node (ref "U11") (pin "25") (pinfunction "SCL/MDC_25") (pintype "bidirectional+no_connect"))
    )
    (net (code "96") (name "unconnected-(U11-SDA{slash}MDIO-Pad26)") (class "Default")
      (node (ref "U11") (pin "26") (pinfunction "SDA/MDIO_26") (pintype "bidirectional+no_connect"))
    )
    (net (code "97") (name "unconnected-(U11-TXONO-Pad46)") (class "Default")
      (node (ref "U11") (pin "46") (pinfunction "TXONO_46") (pintype "bidirectional+no_connect"))
    )
    (net (code "98") (name "unconnected-(U11-TXOPO-Pad47)") (class "Default")
      (node (ref "U11") (pin "47") (pinfunction "TXOPO_47") (pintype "bidirectional+no_connect"))
    )
  )
)
